# YUANLITU.net
KiCad netlist of a schematic drawn in Altium Designer
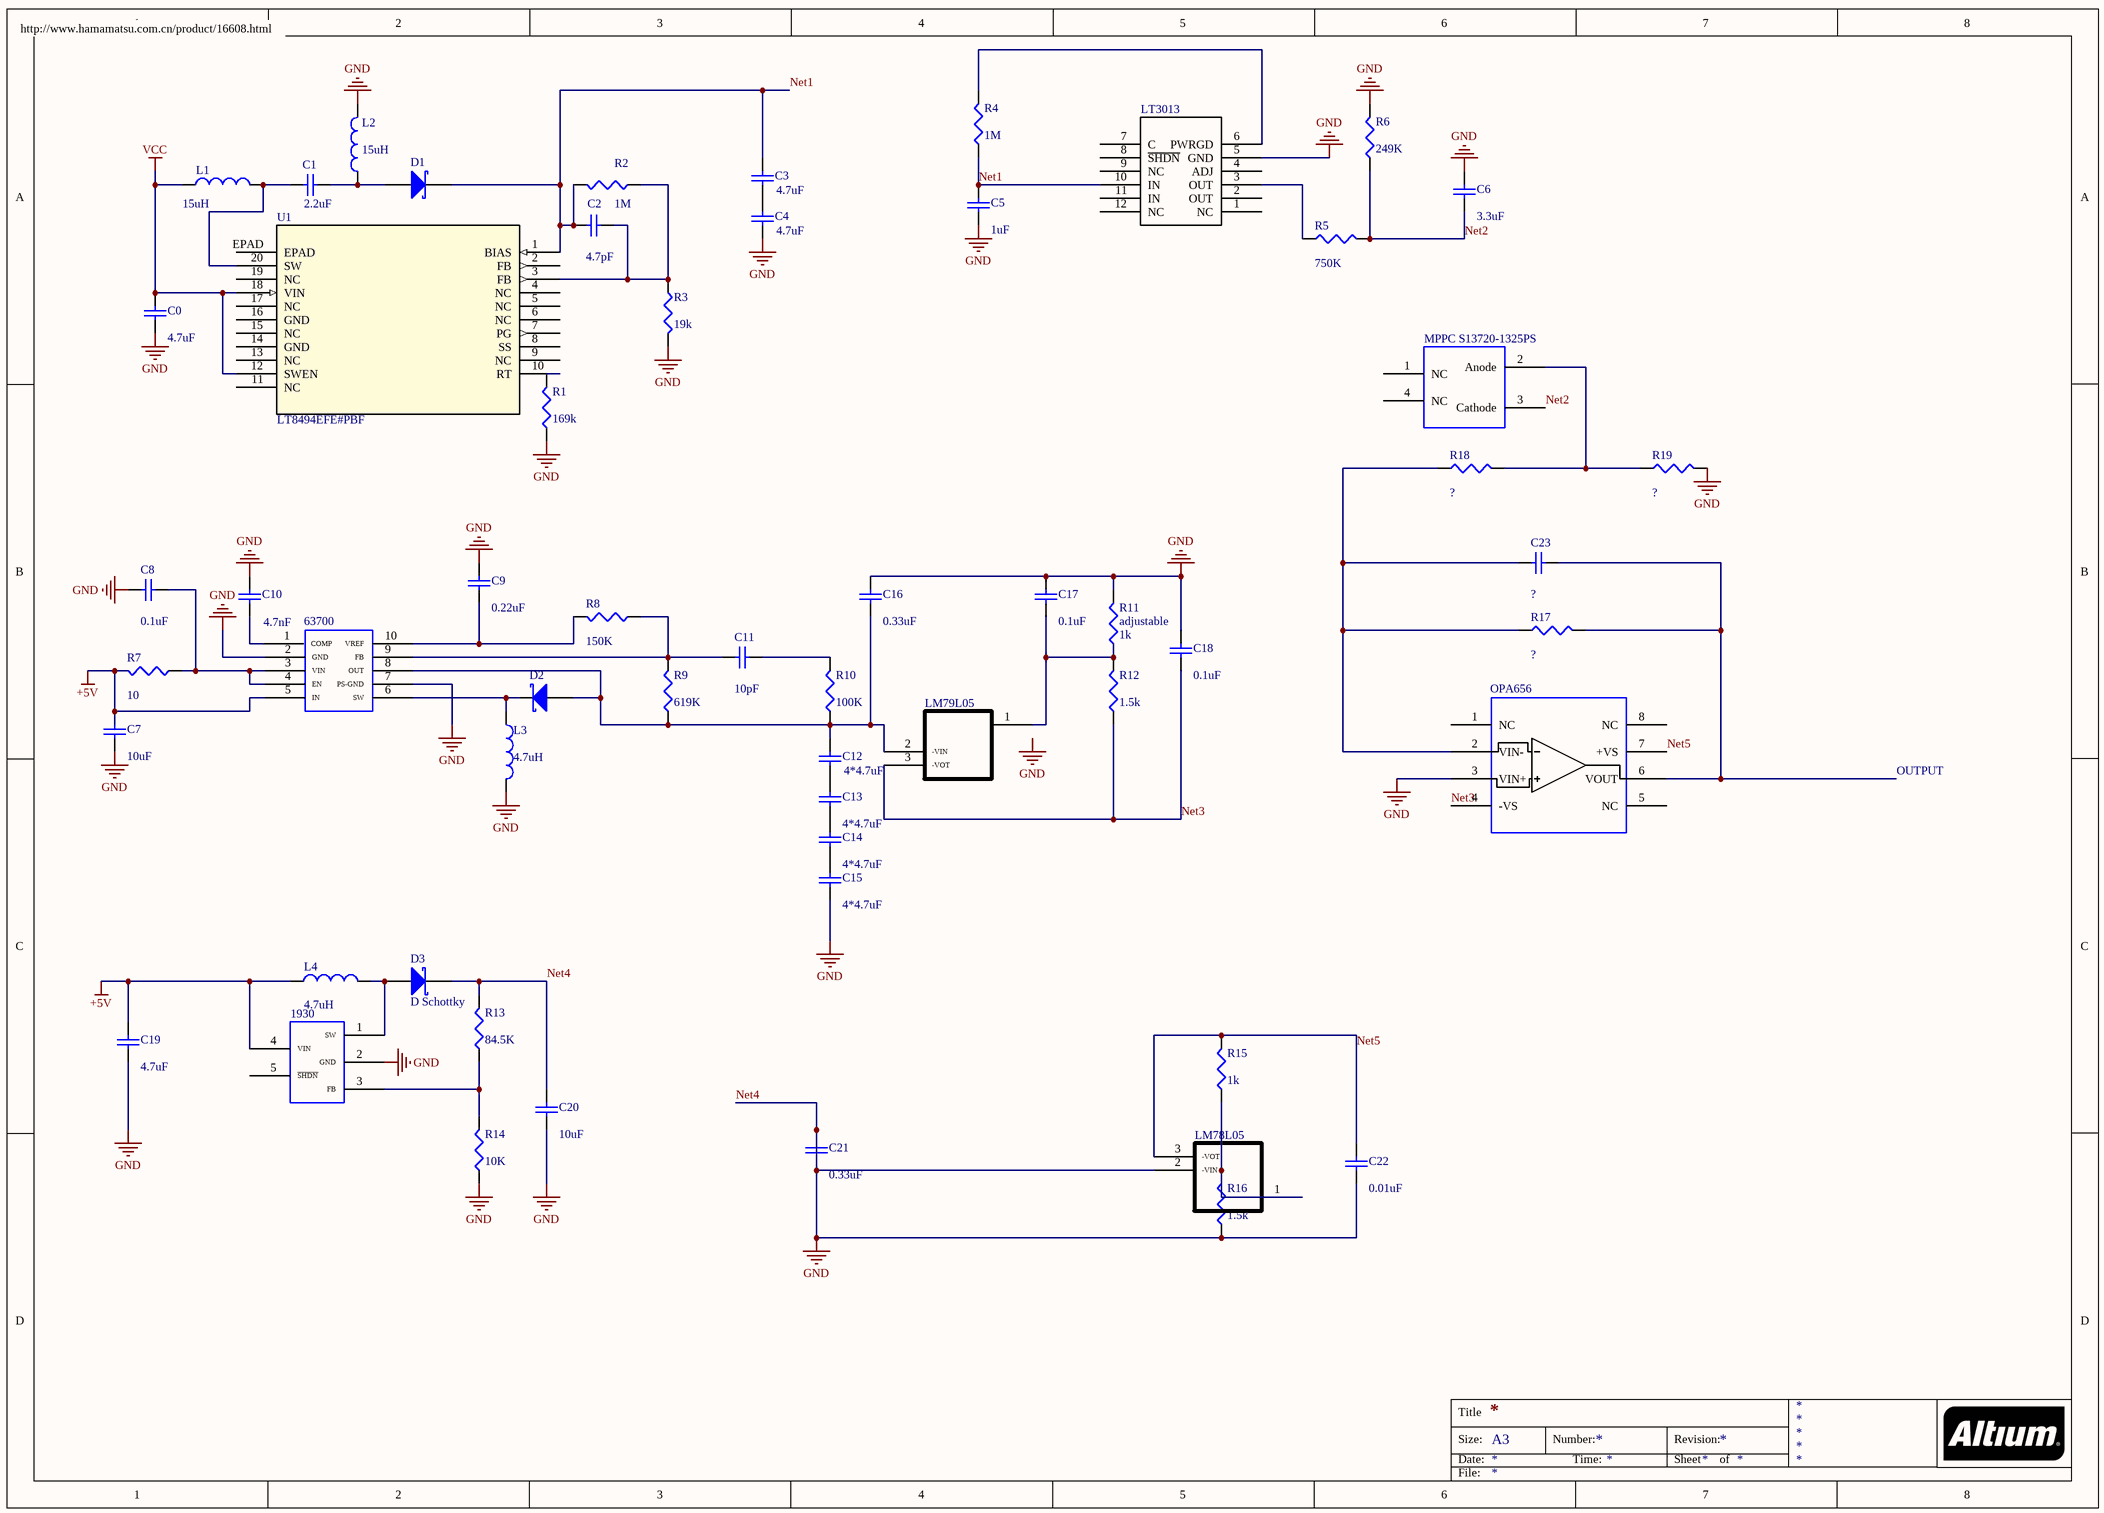
[diagram p0: YUANLITU (1).~(20).~(1).SchDoc]

(export (version "E")
  (design (tool "Eeschema 10.0.6"))
  (components
    (comp (ref "1930") (value "~") (footprint "SOT-23_S5") (libsource (lib "demo2") (part "1930")))
    (comp (ref "63700") (value "~") (footprint "DRC10_2P4X1P65") (libsource (lib "demo2") (part "63700")))
    (comp (ref "C0")
      (value "4.7uF")
      (footprint "0603")
      (description "Capacitor")
      (fields (field (name "PUBLISHER") "Altium Limited"))
      (libsource (lib "Miscellaneous Devices") (part "Cap"))
    )
    (comp (ref "C1")
      (value "2.2uF")
      (footprint "0603")
      (description "Capacitor")
      (fields (field (name "PUBLISHER") "Altium Limited"))
      (libsource (lib "Miscellaneous Devices") (part "Cap"))
    )
    (comp (ref "C2")
      (value "4.7pF")
      (footprint "0603")
      (description "Capacitor")
      (fields (field (name "PUBLISHER") "Altium Limited"))
      (libsource (lib "Miscellaneous Devices") (part "Cap"))
    )
    (comp (ref "C3")
      (value "4.7uF")
      (footprint "C1210")
      (description "Capacitor")
      (fields (field (name "PUBLISHER") "Altium Limited"))
      (libsource (lib "Miscellaneous Devices") (part "Cap"))
    )
    (comp (ref "C4")
      (value "4.7uF")
      (footprint "C1210")
      (description "Capacitor")
      (fields (field (name "PUBLISHER") "Altium Limited"))
      (libsource (lib "Miscellaneous Devices") (part "Cap"))
    )
    (comp (ref "C5")
      (value "1uF")
      (footprint "C1210")
      (description "Capacitor")
      (fields (field (name "PUBLISHER") "Altium Limited"))
      (libsource (lib "Miscellaneous Devices") (part "Cap"))
    )
    (comp (ref "C6")
      (value "3.3uF")
      (footprint "C1210")
      (description "Capacitor")
      (fields (field (name "PUBLISHER") "Altium Limited"))
      (libsource (lib "Miscellaneous Devices") (part "Cap"))
    )
    (comp (ref "C7")
      (value "10uF")
      (footprint "0603")
      (description "Capacitor")
      (fields (field (name "PUBLISHER") "Altium Limited"))
      (libsource (lib "Miscellaneous Devices") (part "Cap"))
    )
    (comp (ref "C8")
      (value "0.1uF")
      (footprint "0603")
      (description "Capacitor")
      (fields (field (name "PUBLISHER") "Altium Limited"))
      (libsource (lib "Miscellaneous Devices") (part "Cap"))
    )
    (comp (ref "C9")
      (value "0.22uF")
      (footprint "0603")
      (description "Capacitor")
      (fields (field (name "PUBLISHER") "Altium Limited"))
      (libsource (lib "Miscellaneous Devices") (part "Cap"))
    )
    (comp (ref "C10")
      (value "4.7nF")
      (footprint "0603")
      (description "Capacitor")
      (fields (field (name "PUBLISHER") "Altium Limited"))
      (libsource (lib "Miscellaneous Devices") (part "Cap"))
    )
    (comp (ref "C11")
      (value "10pF")
      (footprint "0603")
      (description "Capacitor")
      (fields (field (name "PUBLISHER") "Altium Limited"))
      (libsource (lib "Miscellaneous Devices") (part "Cap"))
    )
    (comp (ref "C12")
      (value "4*4.7uF")
      (footprint "0603")
      (description "Capacitor")
      (fields (field (name "PUBLISHER") "Altium Limited"))
      (libsource (lib "Miscellaneous Devices") (part "Cap"))
    )
    (comp (ref "C13")
      (value "4*4.7uF")
      (footprint "0603")
      (description "Capacitor")
      (fields (field (name "PUBLISHER") "Altium Limited"))
      (libsource (lib "Miscellaneous Devices") (part "Cap"))
    )
    (comp (ref "C14")
      (value "4*4.7uF")
      (footprint "0603")
      (description "Capacitor")
      (fields (field (name "PUBLISHER") "Altium Limited"))
      (libsource (lib "Miscellaneous Devices") (part "Cap"))
    )
    (comp (ref "C15")
      (value "4*4.7uF")
      (footprint "0603")
      (description "Capacitor")
      (fields (field (name "PUBLISHER") "Altium Limited"))
      (libsource (lib "Miscellaneous Devices") (part "Cap"))
    )
    (comp (ref "C16")
      (value "0.33uF")
      (footprint "0603")
      (description "Capacitor")
      (fields (field (name "PUBLISHER") "Altium Limited"))
      (libsource (lib "Miscellaneous Devices") (part "Cap"))
    )
    (comp (ref "C17")
      (value "0.1uF")
      (footprint "0603")
      (description "Capacitor")
      (fields (field (name "PUBLISHER") "Altium Limited"))
      (libsource (lib "Miscellaneous Devices") (part "Cap"))
    )
    (comp (ref "C18")
      (value "0.1uF")
      (footprint "0603")
      (description "Capacitor")
      (fields (field (name "PUBLISHER") "Altium Limited"))
      (libsource (lib "Miscellaneous Devices") (part "Cap"))
    )
    (comp (ref "C19")
      (value "4.7uF")
      (footprint "0603")
      (description "Capacitor")
      (fields (field (name "PUBLISHER") "Altium Limited"))
      (libsource (lib "Miscellaneous Devices") (part "Cap"))
    )
    (comp (ref "C20")
      (value "10uF")
      (footprint "0603")
      (description "Capacitor")
      (fields (field (name "PUBLISHER") "Altium Limited"))
      (libsource (lib "Miscellaneous Devices") (part "Cap"))
    )
    (comp (ref "C21")
      (value "0.33uF")
      (footprint "0603")
      (description "Capacitor")
      (fields (field (name "PUBLISHER") "Altium Limited"))
      (libsource (lib "Miscellaneous Devices") (part "Cap"))
    )
    (comp (ref "C22")
      (value "0.01uF")
      (footprint "0603")
      (description "Capacitor")
      (fields (field (name "PUBLISHER") "Altium Limited"))
      (libsource (lib "Miscellaneous Devices") (part "Cap"))
    )
    (comp (ref "C23")
      (value "?")
      (footprint "0603")
      (description "Capacitor")
      (fields (field (name "PUBLISHER") "Altium Limited"))
      (libsource (lib "Miscellaneous Devices") (part "Cap"))
    )
    (comp (ref "D1")
      (value "~")
      (footprint "SMB")
      (description "Schottky Diode")
      (fields (field (name "PUBLISHER") "Altium Limited"))
      (libsource (lib "Miscellaneous Devices") (part "D Schottky"))
    )
    (comp (ref "D2")
      (value "~")
      (footprint "SMB")
      (description "Schottky Diode")
      (fields (field (name "PUBLISHER") "Altium Limited"))
      (libsource (lib "Miscellaneous Devices") (part "D Schottky"))
    )
    (comp (ref "D3")
      (value "D Schottky")
      (footprint "SMB")
      (description "Schottky Diode")
      (fields (field (name "PUBLISHER") "Altium Limited"))
      (libsource (lib "Miscellaneous Devices") (part "D Schottky"))
    )
    (comp (ref "L1")
      (value "15uH")
      (footprint "0603")
      (description "Inductor")
      (fields (field (name "PUBLISHER") "Altium Limited"))
      (libsource (lib "Miscellaneous Devices") (part "Inductor"))
    )
    (comp (ref "L2")
      (value "15uH")
      (footprint "0603")
      (description "Inductor")
      (fields (field (name "PUBLISHER") "Altium Limited"))
      (libsource (lib "Miscellaneous Devices") (part "Inductor"))
    )
    (comp (ref "L3")
      (value "4.7uH")
      (footprint "0603")
      (description "Inductor")
      (fields (field (name "PUBLISHER") "Altium Limited"))
      (libsource (lib "Miscellaneous Devices") (part "Inductor"))
    )
    (comp (ref "L4")
      (value "4.7uH")
      (footprint "0603")
      (description "Inductor")
      (fields (field (name "PUBLISHER") "Altium Limited"))
      (libsource (lib "Miscellaneous Devices") (part "Inductor"))
    )
    (comp (ref "LM78L05") (value "~") (footprint "PCBComponent_1") (libsource (lib "demo2") (part "LM79L05")))
    (comp (ref "LM79L05") (value "~") (footprint "PCBComponent_1") (libsource (lib "") (part "LM79L05_1")))
    (comp (ref "LT3013") (value "~") (footprint "DFN-12_DE") (libsource (lib "LT3013") (part "3013")))
    (comp (ref "MPPC S13720-1325PS")
      (value "~")
      (footprint "PCBComponent_1")
      (libsource (lib "MPPC_S13720-1325PS") (part "MPPC S13720-1325PS"))
    )
    (comp (ref "OPA656") (value "~") (footprint "D8") (libsource (lib "OPA656") (part "OPA656")))
    (comp (ref "R1")
      (value "169k")
      (footprint "0603")
      (description "Resistor")
      (fields (field (name "PUBLISHER") "Altium Limited"))
      (libsource (lib "Miscellaneous Devices") (part "Res3"))
    )
    (comp (ref "R2")
      (value "1M")
      (footprint "0603")
      (description "Resistor")
      (fields (field (name "PUBLISHER") "Altium Limited"))
      (libsource (lib "Miscellaneous Devices") (part "Res3"))
    )
    (comp (ref "R3")
      (value "19k")
      (footprint "0603")
      (description "Resistor")
      (fields (field (name "PUBLISHER") "Altium Limited"))
      (libsource (lib "Miscellaneous Devices") (part "Res3"))
    )
    (comp (ref "R4")
      (value "1M")
      (footprint "0603")
      (description "Resistor")
      (fields (field (name "PUBLISHER") "Altium Limited"))
      (libsource (lib "Miscellaneous Devices") (part "Res3"))
    )
    (comp (ref "R5")
      (value "750K")
      (footprint "0603")
      (description "Resistor")
      (fields (field (name "PUBLISHER") "Altium Limited"))
      (libsource (lib "Miscellaneous Devices") (part "Res3"))
    )
    (comp (ref "R6")
      (value "249K")
      (footprint "0603")
      (description "Resistor")
      (fields (field (name "PUBLISHER") "Altium Limited"))
      (libsource (lib "Miscellaneous Devices") (part "Res3"))
    )
    (comp (ref "R7")
      (value "10")
      (footprint "0603")
      (description "Resistor")
      (fields (field (name "PUBLISHER") "Altium Limited"))
      (libsource (lib "Miscellaneous Devices") (part "Res3"))
    )
    (comp (ref "R8")
      (value "150K")
      (footprint "0603")
      (description "Resistor")
      (fields (field (name "PUBLISHER") "Altium Limited"))
      (libsource (lib "Miscellaneous Devices") (part "Res3"))
    )
    (comp (ref "R9")
      (value "619K")
      (footprint "0603")
      (description "Resistor")
      (fields (field (name "PUBLISHER") "Altium Limited"))
      (libsource (lib "Miscellaneous Devices") (part "Res3"))
    )
    (comp (ref "R10")
      (value "100K")
      (footprint "0603")
      (description "Resistor")
      (fields (field (name "PUBLISHER") "Altium Limited"))
      (libsource (lib "Miscellaneous Devices") (part "Res3"))
    )
    (comp (ref "R11")
      (value "adjustable")
      (footprint "0603")
      (description "Resistor")
      (fields (field (name "ALTIUM_VALUE") "1k") (field (name "PUBLISHER") "Altium Limited"))
      (libsource (lib "Miscellaneous Devices") (part "Res3"))
    )
    (comp (ref "R12")
      (value "1.5k")
      (footprint "0603")
      (description "Resistor")
      (fields (field (name "PUBLISHER") "Altium Limited"))
      (libsource (lib "Miscellaneous Devices") (part "Res3"))
    )
    (comp (ref "R13")
      (value "84.5K")
      (footprint "0603")
      (description "Resistor")
      (fields (field (name "PUBLISHER") "Altium Limited"))
      (libsource (lib "Miscellaneous Devices") (part "Res3"))
    )
    (comp (ref "R14")
      (value "10K")
      (footprint "J1-0603")
      (description "Resistor")
      (fields (field (name "PUBLISHER") "Altium Limited"))
      (libsource (lib "Miscellaneous Devices") (part "Res3"))
    )
    (comp (ref "R15")
      (value "1k")
      (footprint "J1-0603")
      (description "Resistor")
      (fields (field (name "PUBLISHER") "Altium Limited"))
      (libsource (lib "Miscellaneous Devices") (part "Res3"))
    )
    (comp (ref "R16")
      (value "1.5k")
      (footprint "J1-0603")
      (description "Resistor")
      (fields (field (name "PUBLISHER") "Altium Limited"))
      (libsource (lib "Miscellaneous Devices") (part "Res3"))
    )
    (comp (ref "R17")
      (value "?")
      (footprint "J1-0603")
      (description "Resistor")
      (fields (field (name "PUBLISHER") "Altium Limited"))
      (libsource (lib "Miscellaneous Devices") (part "Res3"))
    )
    (comp (ref "R18")
      (value "?")
      (footprint "J1-0603")
      (description "Resistor")
      (fields (field (name "PUBLISHER") "Altium Limited"))
      (libsource (lib "Miscellaneous Devices") (part "Res3"))
    )
    (comp (ref "R19")
      (value "?")
      (footprint "J1-0603")
      (description "Resistor")
      (fields (field (name "PUBLISHER") "Altium Limited"))
      (libsource (lib "Miscellaneous Devices") (part "Res3"))
    )
    (comp (ref "U1")
      (value "LT8494EFE#PBF")
      (footprint "TSSOP-20_FE/CB")
      (description "Imported")
      (fields (field (name "MANUFACTURER_PART_NUMBER") "lt8494efe#pbf"))
      (libsource (lib "8494") (part "LT8494EFE#PBF"))
    )
  )
  (nets
    (net (code "1") (name "+5V") (class "Default")
      (node (ref "1930") (pin "4") (pinfunction "VIN_4") (pintype "passive"))
      (node (ref "63700") (pin "5") (pinfunction "IN_5") (pintype "passive"))
      (node (ref "C19") (pin "2") (pinfunction "2_2") (pintype "passive"))
      (node (ref "C7") (pin "2") (pinfunction "2_2") (pintype "passive"))
      (node (ref "L4") (pin "1") (pinfunction "1_1") (pintype "passive"))
      (node (ref "R7") (pin "2") (pinfunction "2_2") (pintype "passive"))
    )
    (net (code "2") (name "/Net1") (class "Default")
      (node (ref "C2") (pin "2") (pinfunction "2_2") (pintype "passive"))
      (node (ref "C3") (pin "1") (pinfunction "1_1") (pintype "passive"))
      (node (ref "C5") (pin "2") (pinfunction "2_2") (pintype "passive"))
      (node (ref "D1") (pin "2") (pinfunction "K_2") (pintype "passive"))
      (node (ref "LT3013") (pin "10") (pinfunction "IN_10") (pintype "passive"))
      (node (ref "R2") (pin "2") (pinfunction "2_2") (pintype "passive"))
      (node (ref "R4") (pin "1") (pinfunction "1_1") (pintype "passive"))
      (node (ref "U1") (pin "1") (pinfunction "BIAS_1") (pintype "input"))
    )
    (net (code "3") (name "/Net2") (class "Default")
      (node (ref "C6") (pin "1") (pinfunction "1_1") (pintype "passive"))
      (node (ref "MPPC S13720-1325PS") (pin "3") (pinfunction "Cathode_3") (pintype "passive"))
      (node (ref "R5") (pin "2") (pinfunction "2_2") (pintype "passive"))
      (node (ref "R6") (pin "1") (pinfunction "1_1") (pintype "passive"))
    )
    (net (code "4") (name "/Net3") (class "Default")
      (node (ref "C18") (pin "1") (pinfunction "1_1") (pintype "passive"))
      (node (ref "LM79L05") (pin "3") (pinfunction "-VOT_3") (pintype "passive"))
      (node (ref "OPA656") (pin "4") (pinfunction "-VS_4") (pintype "passive"))
      (node (ref "R12") (pin "1") (pinfunction "1_1") (pintype "passive"))
    )
    (net (code "5") (name "/Net5") (class "Default")
      (node (ref "C22") (pin "2") (pinfunction "2_2") (pintype "passive"))
      (node (ref "LM78L05") (pin "3") (pinfunction "-VOT_3") (pintype "passive"))
      (node (ref "OPA656") (pin "7") (pinfunction "+VS_7") (pintype "passive"))
      (node (ref "R15") (pin "2") (pinfunction "2_2") (pintype "passive"))
    )
    (net (code "6") (name "GND") (class "Default")
      (node (ref "1930") (pin "2") (pinfunction "GND_2") (pintype "passive"))
      (node (ref "63700") (pin "2") (pinfunction "GND_2") (pintype "passive"))
      (node (ref "63700") (pin "7") (pinfunction "PS-GND_7") (pintype "passive"))
      (node (ref "C0") (pin "1") (pinfunction "1_1") (pintype "passive"))
      (node (ref "C10") (pin "2") (pinfunction "2_2") (pintype "passive"))
      (node (ref "C15") (pin "1") (pinfunction "1_1") (pintype "passive"))
      (node (ref "C16") (pin "1") (pinfunction "1_1") (pintype "passive"))
      (node (ref "C17") (pin "1") (pinfunction "1_1") (pintype "passive"))
      (node (ref "C18") (pin "2") (pinfunction "2_2") (pintype "passive"))
      (node (ref "C19") (pin "1") (pinfunction "1_1") (pintype "passive"))
      (node (ref "C20") (pin "1") (pinfunction "1_1") (pintype "passive"))
      (node (ref "C20") (pin "2") (pinfunction "2_2") (pintype "passive"))
      (node (ref "C21") (pin "1") (pinfunction "1_1") (pintype "passive"))
      (node (ref "C21") (pin "2") (pinfunction "2_2") (pintype "passive"))
      (node (ref "C22") (pin "1") (pinfunction "1_1") (pintype "passive"))
      (node (ref "C4") (pin "2") (pinfunction "2_2") (pintype "passive"))
      (node (ref "C5") (pin "1") (pinfunction "1_1") (pintype "passive"))
      (node (ref "C6") (pin "2") (pinfunction "2_2") (pintype "passive"))
      (node (ref "C7") (pin "1") (pinfunction "1_1") (pintype "passive"))
      (node (ref "C8") (pin "1") (pinfunction "1_1") (pintype "passive"))
      (node (ref "C9") (pin "2") (pinfunction "2_2") (pintype "passive"))
      (node (ref "D3") (pin "2") (pinfunction "K_2") (pintype "passive"))
      (node (ref "L2") (pin "2") (pinfunction "2_2") (pintype "passive"))
      (node (ref "L3") (pin "2") (pinfunction "2_2") (pintype "passive"))
      (node (ref "LM78L05") (pin "2") (pinfunction "-VIN_2") (pintype "passive"))
      (node (ref "LT3013") (pin "5") (pinfunction "GND_5") (pintype "passive"))
      (node (ref "OPA656") (pin "3") (pinfunction "VIN+_3") (pintype "passive"))
      (node (ref "R1") (pin "1") (pinfunction "1_1") (pintype "passive"))
      (node (ref "R11") (pin "2") (pinfunction "2_2") (pintype "passive"))
      (node (ref "R13") (pin "2") (pinfunction "2_2") (pintype "passive"))
      (node (ref "R14") (pin "1") (pinfunction "1_1") (pintype "passive"))
      (node (ref "R16") (pin "1") (pinfunction "1_1") (pintype "passive"))
      (node (ref "R19") (pin "2") (pinfunction "2_2") (pintype "passive"))
      (node (ref "R3") (pin "2") (pinfunction "2_2") (pintype "passive"))
      (node (ref "R6") (pin "2") (pinfunction "2_2") (pintype "passive"))
    )
    (net (code "7") (name "Net-(1930-FB)") (class "Default")
      (node (ref "1930") (pin "3") (pinfunction "FB_3") (pintype "passive"))
      (node (ref "R13") (pin "1") (pinfunction "1_1") (pintype "passive"))
      (node (ref "R14") (pin "2") (pinfunction "2_2") (pintype "passive"))
    )
    (net (code "8") (name "Net-(1930-SW)") (class "Default")
      (node (ref "1930") (pin "1") (pinfunction "SW_1") (pintype "passive"))
      (node (ref "D3") (pin "1") (pinfunction "A_1") (pintype "passive"))
      (node (ref "L4") (pin "2") (pinfunction "2_2") (pintype "passive"))
    )
    (net (code "9") (name "Net-(63700-COMP)") (class "Default")
      (node (ref "63700") (pin "1") (pinfunction "COMP_1") (pintype "open_collector"))
      (node (ref "C10") (pin "1") (pinfunction "1_1") (pintype "passive"))
    )
    (net (code "10") (name "Net-(63700-EN)") (class "Default")
      (node (ref "63700") (pin "3") (pinfunction "VIN_3") (pintype "passive"))
      (node (ref "63700") (pin "4") (pinfunction "EN_4") (pintype "passive"))
      (node (ref "C8") (pin "2") (pinfunction "2_2") (pintype "passive"))
      (node (ref "R7") (pin "1") (pinfunction "1_1") (pintype "passive"))
    )
    (net (code "11") (name "Net-(63700-FB)") (class "Default")
      (node (ref "63700") (pin "9") (pinfunction "FB_9") (pintype "passive"))
      (node (ref "C11") (pin "1") (pinfunction "1_1") (pintype "passive"))
      (node (ref "R8") (pin "1") (pinfunction "1_1") (pintype "passive"))
      (node (ref "R9") (pin "2") (pinfunction "2_2") (pintype "passive"))
    )
    (net (code "12") (name "Net-(63700-OUT)") (class "Default")
      (node (ref "63700") (pin "8") (pinfunction "OUT_8") (pintype "passive"))
      (node (ref "C12") (pin "2") (pinfunction "2_2") (pintype "passive"))
      (node (ref "C16") (pin "2") (pinfunction "2_2") (pintype "passive"))
      (node (ref "D2") (pin "1") (pinfunction "A_1") (pintype "passive"))
      (node (ref "LM79L05") (pin "2") (pinfunction "-VIN_2") (pintype "passive"))
      (node (ref "R10") (pin "1") (pinfunction "1_1") (pintype "passive"))
      (node (ref "R9") (pin "1") (pinfunction "1_1") (pintype "passive"))
    )
    (net (code "13") (name "Net-(63700-SW)") (class "Default")
      (node (ref "63700") (pin "6") (pinfunction "SW_6") (pintype "passive"))
      (node (ref "D2") (pin "2") (pinfunction "K_2") (pintype "passive"))
      (node (ref "L3") (pin "1") (pinfunction "1_1") (pintype "passive"))
    )
    (net (code "14") (name "Net-(63700-VREF)") (class "Default")
      (node (ref "63700") (pin "10") (pinfunction "VREF_10") (pintype "passive"))
      (node (ref "C9") (pin "1") (pinfunction "1_1") (pintype "passive"))
      (node (ref "R8") (pin "2") (pinfunction "2_2") (pintype "passive"))
    )
    (net (code "15") (name "Net-(C2-Pad1)") (class "Default")
      (node (ref "C2") (pin "1") (pinfunction "1_1") (pintype "passive"))
      (node (ref "R2") (pin "1") (pinfunction "1_1") (pintype "passive"))
      (node (ref "R3") (pin "1") (pinfunction "1_1") (pintype "passive"))
      (node (ref "U1") (pin "3") (pinfunction "FB_3") (pintype "output"))
    )
    (net (code "16") (name "Net-(C3-Pad2)") (class "Default")
      (node (ref "C3") (pin "2") (pinfunction "2_2") (pintype "passive"))
      (node (ref "C4") (pin "1") (pinfunction "1_1") (pintype "passive"))
    )
    (net (code "17") (name "Net-(C11-Pad2)") (class "Default")
      (node (ref "C11") (pin "2") (pinfunction "2_2") (pintype "passive"))
      (node (ref "R10") (pin "2") (pinfunction "2_2") (pintype "passive"))
    )
    (net (code "18") (name "Net-(C12-Pad1)") (class "Default")
      (node (ref "C12") (pin "1") (pinfunction "1_1") (pintype "passive"))
      (node (ref "C13") (pin "2") (pinfunction "2_2") (pintype "passive"))
    )
    (net (code "19") (name "Net-(C13-Pad1)") (class "Default")
      (node (ref "C13") (pin "1") (pinfunction "1_1") (pintype "passive"))
      (node (ref "C14") (pin "2") (pinfunction "2_2") (pintype "passive"))
    )
    (net (code "20") (name "Net-(C14-Pad1)") (class "Default")
      (node (ref "C14") (pin "1") (pinfunction "1_1") (pintype "passive"))
      (node (ref "C15") (pin "2") (pinfunction "2_2") (pintype "passive"))
    )
    (net (code "21") (name "Net-(C17-Pad2)") (class "Default")
      (node (ref "C17") (pin "2") (pinfunction "2_2") (pintype "passive"))
      (node (ref "LM79L05") (pin "1") (pintype "passive"))
      (node (ref "R11") (pin "1") (pinfunction "1_1") (pintype "passive"))
      (node (ref "R12") (pin "2") (pinfunction "2_2") (pintype "passive"))
    )
    (net (code "22") (name "Net-(D1-A)") (class "Default")
      (node (ref "C1") (pin "1") (pinfunction "1_1") (pintype "passive"))
      (node (ref "D1") (pin "1") (pinfunction "A_1") (pintype "passive"))
      (node (ref "L2") (pin "1") (pinfunction "1_1") (pintype "passive"))
    )
    (net (code "23") (name "Net-(LM78L05-Pad1)") (class "Default")
      (node (ref "LM78L05") (pin "1") (pintype "passive"))
      (node (ref "R15") (pin "1") (pinfunction "1_1") (pintype "passive"))
      (node (ref "R16") (pin "2") (pinfunction "2_2") (pintype "passive"))
    )
    (net (code "24") (name "Net-(LT3013-OUT-Pad3)") (class "Default")
      (node (ref "LT3013") (pin "3") (pinfunction "OUT_3") (pintype "passive"))
      (node (ref "R5") (pin "1") (pinfunction "1_1") (pintype "passive"))
    )
    (net (code "25") (name "Net-(LT3013-PWRGD)") (class "Default")
      (node (ref "LT3013") (pin "6") (pinfunction "PWRGD_6") (pintype "passive"))
      (node (ref "R4") (pin "2") (pinfunction "2_2") (pintype "passive"))
    )
    (net (code "26") (name "Net-(MPPC S13720-1325PS-Anode)") (class "Default")
      (node (ref "MPPC S13720-1325PS") (pin "2") (pinfunction "Anode_2") (pintype "passive"))
      (node (ref "R18") (pin "2") (pinfunction "2_2") (pintype "passive"))
      (node (ref "R19") (pin "1") (pinfunction "1_1") (pintype "passive"))
    )
    (net (code "27") (name "Net-(OPA656-VIN-)") (class "Default")
      (node (ref "C23") (pin "1") (pinfunction "1_1") (pintype "passive"))
      (node (ref "OPA656") (pin "2") (pinfunction "VIN-_2") (pintype "passive"))
      (node (ref "R17") (pin "1") (pinfunction "1_1") (pintype "passive"))
      (node (ref "R18") (pin "1") (pinfunction "1_1") (pintype "passive"))
    )
    (net (code "28") (name "Net-(OPA656-VOUT)") (class "Default")
      (node (ref "C23") (pin "2") (pinfunction "2_2") (pintype "passive"))
      (node (ref "OPA656") (pin "6") (pinfunction "VOUT_6") (pintype "passive"))
      (node (ref "R17") (pin "2") (pinfunction "2_2") (pintype "passive"))
    )
    (net (code "29") (name "Net-(U1-RT)") (class "Default")
      (node (ref "R1") (pin "2") (pinfunction "2_2") (pintype "passive"))
      (node (ref "U1") (pin "10") (pinfunction "RT_10") (pintype "passive"))
    )
    (net (code "30") (name "Net-(U1-SW)") (class "Default")
      (node (ref "C1") (pin "2") (pinfunction "2_2") (pintype "passive"))
      (node (ref "L1") (pin "2") (pinfunction "2_2") (pintype "passive"))
      (node (ref "U1") (pin "20") (pinfunction "SW_20") (pintype "passive"))
    )
    (net (code "31") (name "VCC") (class "Default")
      (node (ref "C0") (pin "2") (pinfunction "2_2") (pintype "passive"))
      (node (ref "L1") (pin "1") (pinfunction "1_1") (pintype "passive"))
      (node (ref "U1") (pin "12") (pinfunction "SWEN_12") (pintype "passive"))
      (node (ref "U1") (pin "18") (pinfunction "VIN_18") (pintype "input"))
    )
    (net (code "32") (name "unconnected-(1930-~{SHDN}-Pad5)") (class "Default")
      (node (ref "1930") (pin "5") (pinfunction "~{SHDN}_5") (pintype "passive"))
    )
    (net (code "33") (name "unconnected-(LT3013-ADJ-Pad4)") (class "Default")
      (node (ref "LT3013") (pin "4") (pinfunction "ADJ_4") (pintype "passive"))
    )
    (net (code "34") (name "unconnected-(LT3013-C-Pad7)") (class "Default")
      (node (ref "LT3013") (pin "7") (pinfunction "C_7") (pintype "passive"))
    )
    (net (code "35") (name "unconnected-(LT3013-IN-Pad11)") (class "Default")
      (node (ref "LT3013") (pin "11") (pinfunction "IN_11") (pintype "passive"))
    )
    (net (code "36") (name "unconnected-(LT3013-NC-Pad1)") (class "Default")
      (node (ref "LT3013") (pin "1") (pinfunction "NC_1") (pintype "passive"))
    )
    (net (code "37") (name "unconnected-(LT3013-NC-Pad9)") (class "Default")
      (node (ref "LT3013") (pin "9") (pinfunction "NC_9") (pintype "passive"))
    )
    (net (code "38") (name "unconnected-(LT3013-NC-Pad12)") (class "Default")
      (node (ref "LT3013") (pin "12") (pinfunction "NC_12") (pintype "passive"))
    )
    (net (code "39") (name "unconnected-(LT3013-OUT-Pad2)") (class "Default")
      (node (ref "LT3013") (pin "2") (pinfunction "OUT_2") (pintype "passive"))
    )
    (net (code "40") (name "unconnected-(LT3013-~{SHDN}-Pad8)") (class "Default")
      (node (ref "LT3013") (pin "8") (pinfunction "~{SHDN}_8") (pintype "passive"))
    )
    (net (code "41") (name "unconnected-(MPPC S13720-1325PS-NC-Pad1)") (class "Default")
      (node (ref "MPPC S13720-1325PS") (pin "1") (pinfunction "NC_1") (pintype "passive"))
    )
    (net (code "42") (name "unconnected-(MPPC S13720-1325PS-NC-Pad4)") (class "Default")
      (node (ref "MPPC S13720-1325PS") (pin "4") (pinfunction "NC_4") (pintype "passive"))
    )
    (net (code "43") (name "unconnected-(OPA656-NC-Pad1)") (class "Default")
      (node (ref "OPA656") (pin "1") (pinfunction "NC_1") (pintype "passive"))
    )
    (net (code "44") (name "unconnected-(OPA656-NC-Pad5)") (class "Default")
      (node (ref "OPA656") (pin "5") (pinfunction "NC_5") (pintype "passive"))
    )
    (net (code "45") (name "unconnected-(OPA656-NC-Pad8)") (class "Default")
      (node (ref "OPA656") (pin "8") (pinfunction "NC_8") (pintype "passive"))
    )
    (net (code "46") (name "unconnected-(U1-FB-Pad2)") (class "Default")
      (node (ref "U1") (pin "2") (pinfunction "FB_2") (pintype "output"))
    )
    (net (code "47") (name "unconnected-(U1-GND-Pad14)") (class "Default")
      (node (ref "U1") (pin "14") (pinfunction "GND_14") (pintype "power_in"))
    )
    (net (code "48") (name "unconnected-(U1-GND-Pad16)") (class "Default")
      (node (ref "U1") (pin "16") (pinfunction "GND_16") (pintype "power_in"))
    )
    (net (code "49") (name "unconnected-(U1-NC-Pad4)") (class "Default")
      (node (ref "U1") (pin "4") (pinfunction "NC_4") (pintype "passive"))
    )
    (net (code "50") (name "unconnected-(U1-NC-Pad5)") (class "Default")
      (node (ref "U1") (pin "5") (pinfunction "NC_5") (pintype "passive"))
    )
    (net (code "51") (name "unconnected-(U1-NC-Pad6)") (class "Default")
      (node (ref "U1") (pin "6") (pinfunction "NC_6") (pintype "passive"))
    )
    (net (code "52") (name "unconnected-(U1-NC-Pad9)") (class "Default")
      (node (ref "U1") (pin "9") (pinfunction "NC_9") (pintype "passive"))
    )
    (net (code "53") (name "unconnected-(U1-NC-Pad11)") (class "Default")
      (node (ref "U1") (pin "11") (pinfunction "NC_11") (pintype "passive"))
    )
    (net (code "54") (name "unconnected-(U1-NC-Pad13)") (class "Default")
      (node (ref "U1") (pin "13") (pinfunction "NC_13") (pintype "passive"))
    )
    (net (code "55") (name "unconnected-(U1-NC-Pad15)") (class "Default")
      (node (ref "U1") (pin "15") (pinfunction "NC_15") (pintype "passive"))
    )
    (net (code "56") (name "unconnected-(U1-NC-Pad17)") (class "Default")
      (node (ref "U1") (pin "17") (pinfunction "NC_17") (pintype "passive"))
    )
    (net (code "57") (name "unconnected-(U1-NC-Pad19)") (class "Default")
      (node (ref "U1") (pin "19") (pinfunction "NC_19") (pintype "passive"))
    )
    (net (code "58") (name "unconnected-(U1-PG-Pad7)") (class "Default")
      (node (ref "U1") (pin "7") (pinfunction "PG_7") (pintype "output"))
    )
    (net (code "59") (name "unconnected-(U1-PadEPAD)") (class "Default")
      (node (ref "U1") (pin "EPAD") (pinfunction "EPAD_EPAD") (pintype "passive"))
    )
    (net (code "60") (name "unconnected-(U1-SS-Pad8)") (class "Default")
      (node (ref "U1") (pin "8") (pinfunction "SS_8") (pintype "passive"))
    )
  )
)
